# Shield.net
KiCad netlist of a schematic drawn in EAGLE
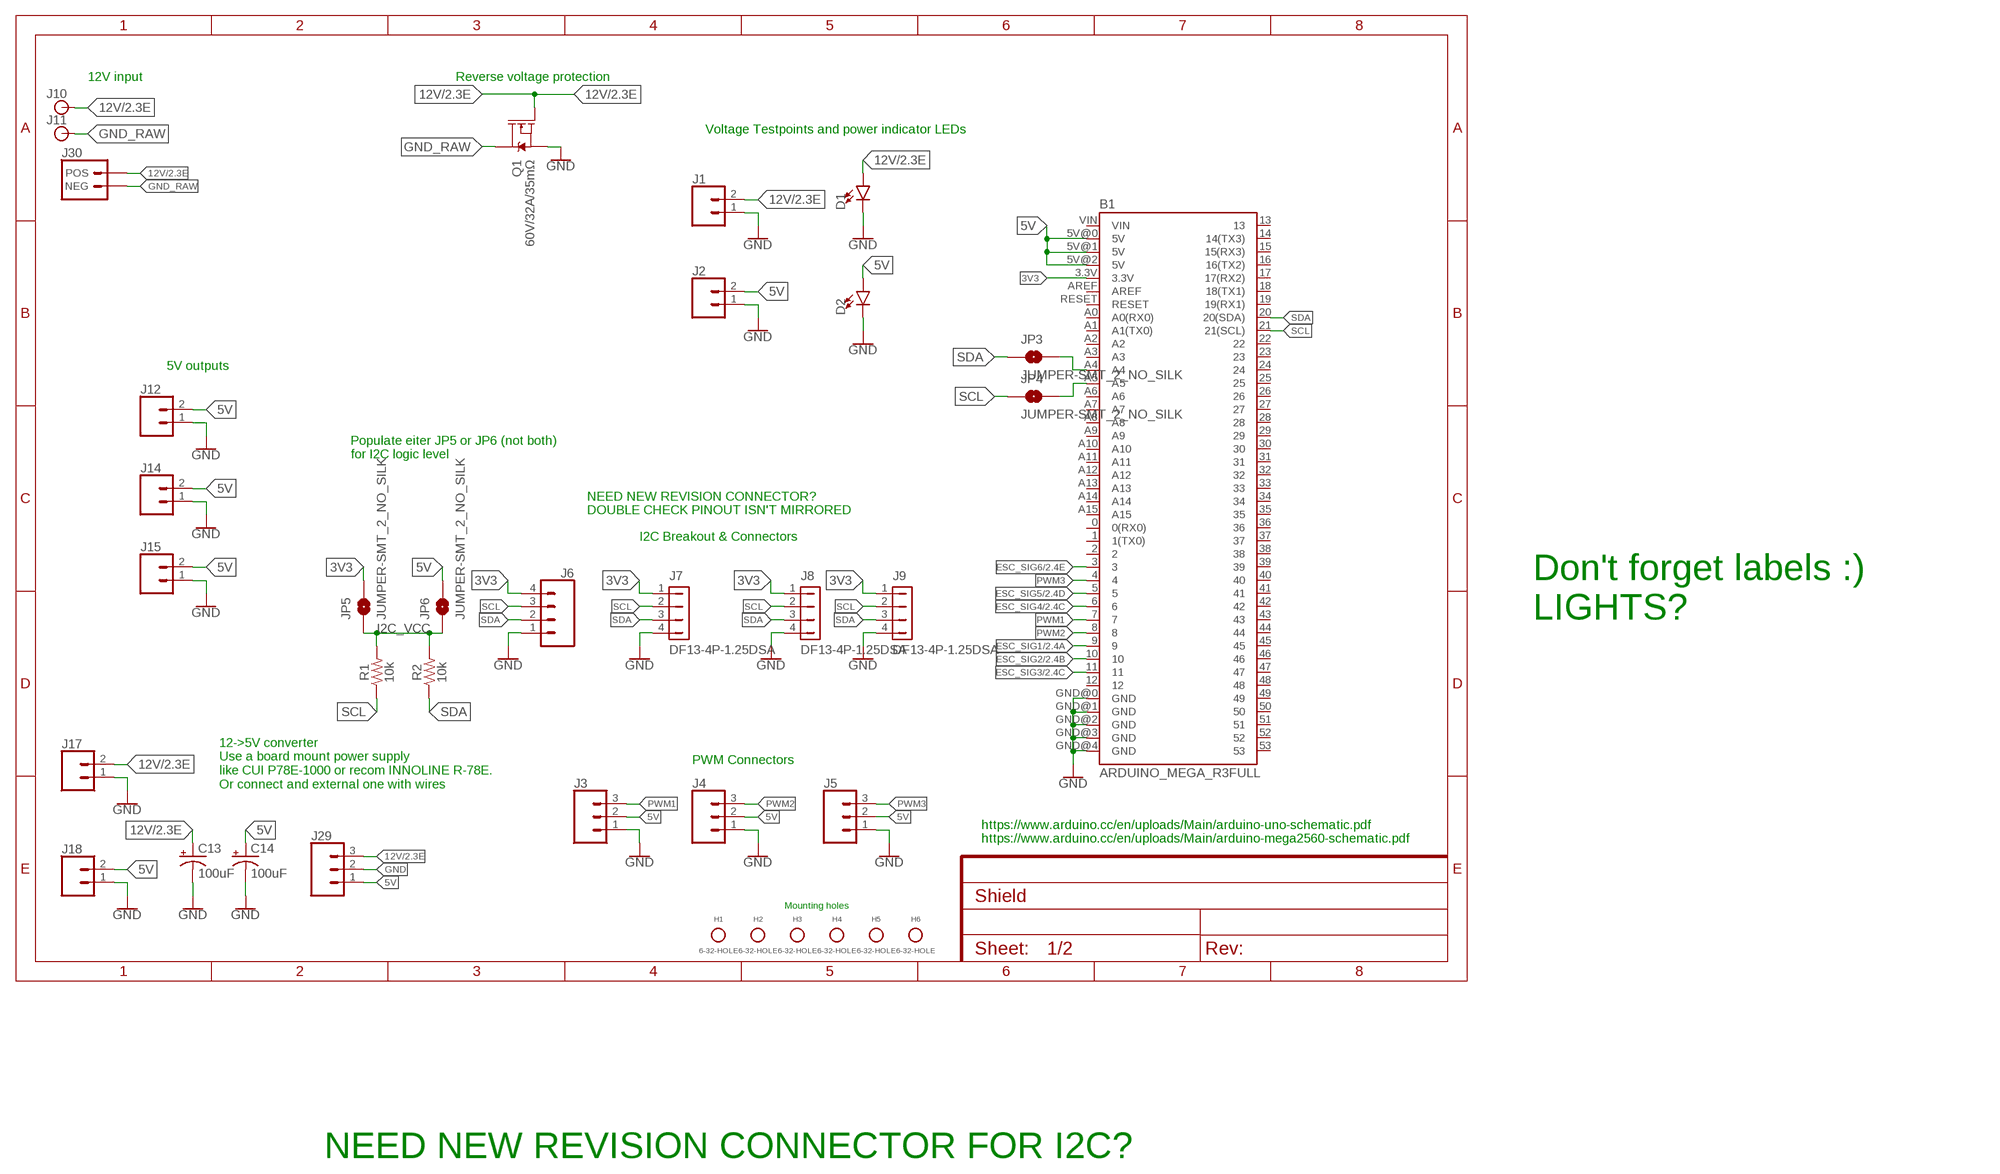
[diagram p0: schematic, sheet 1]
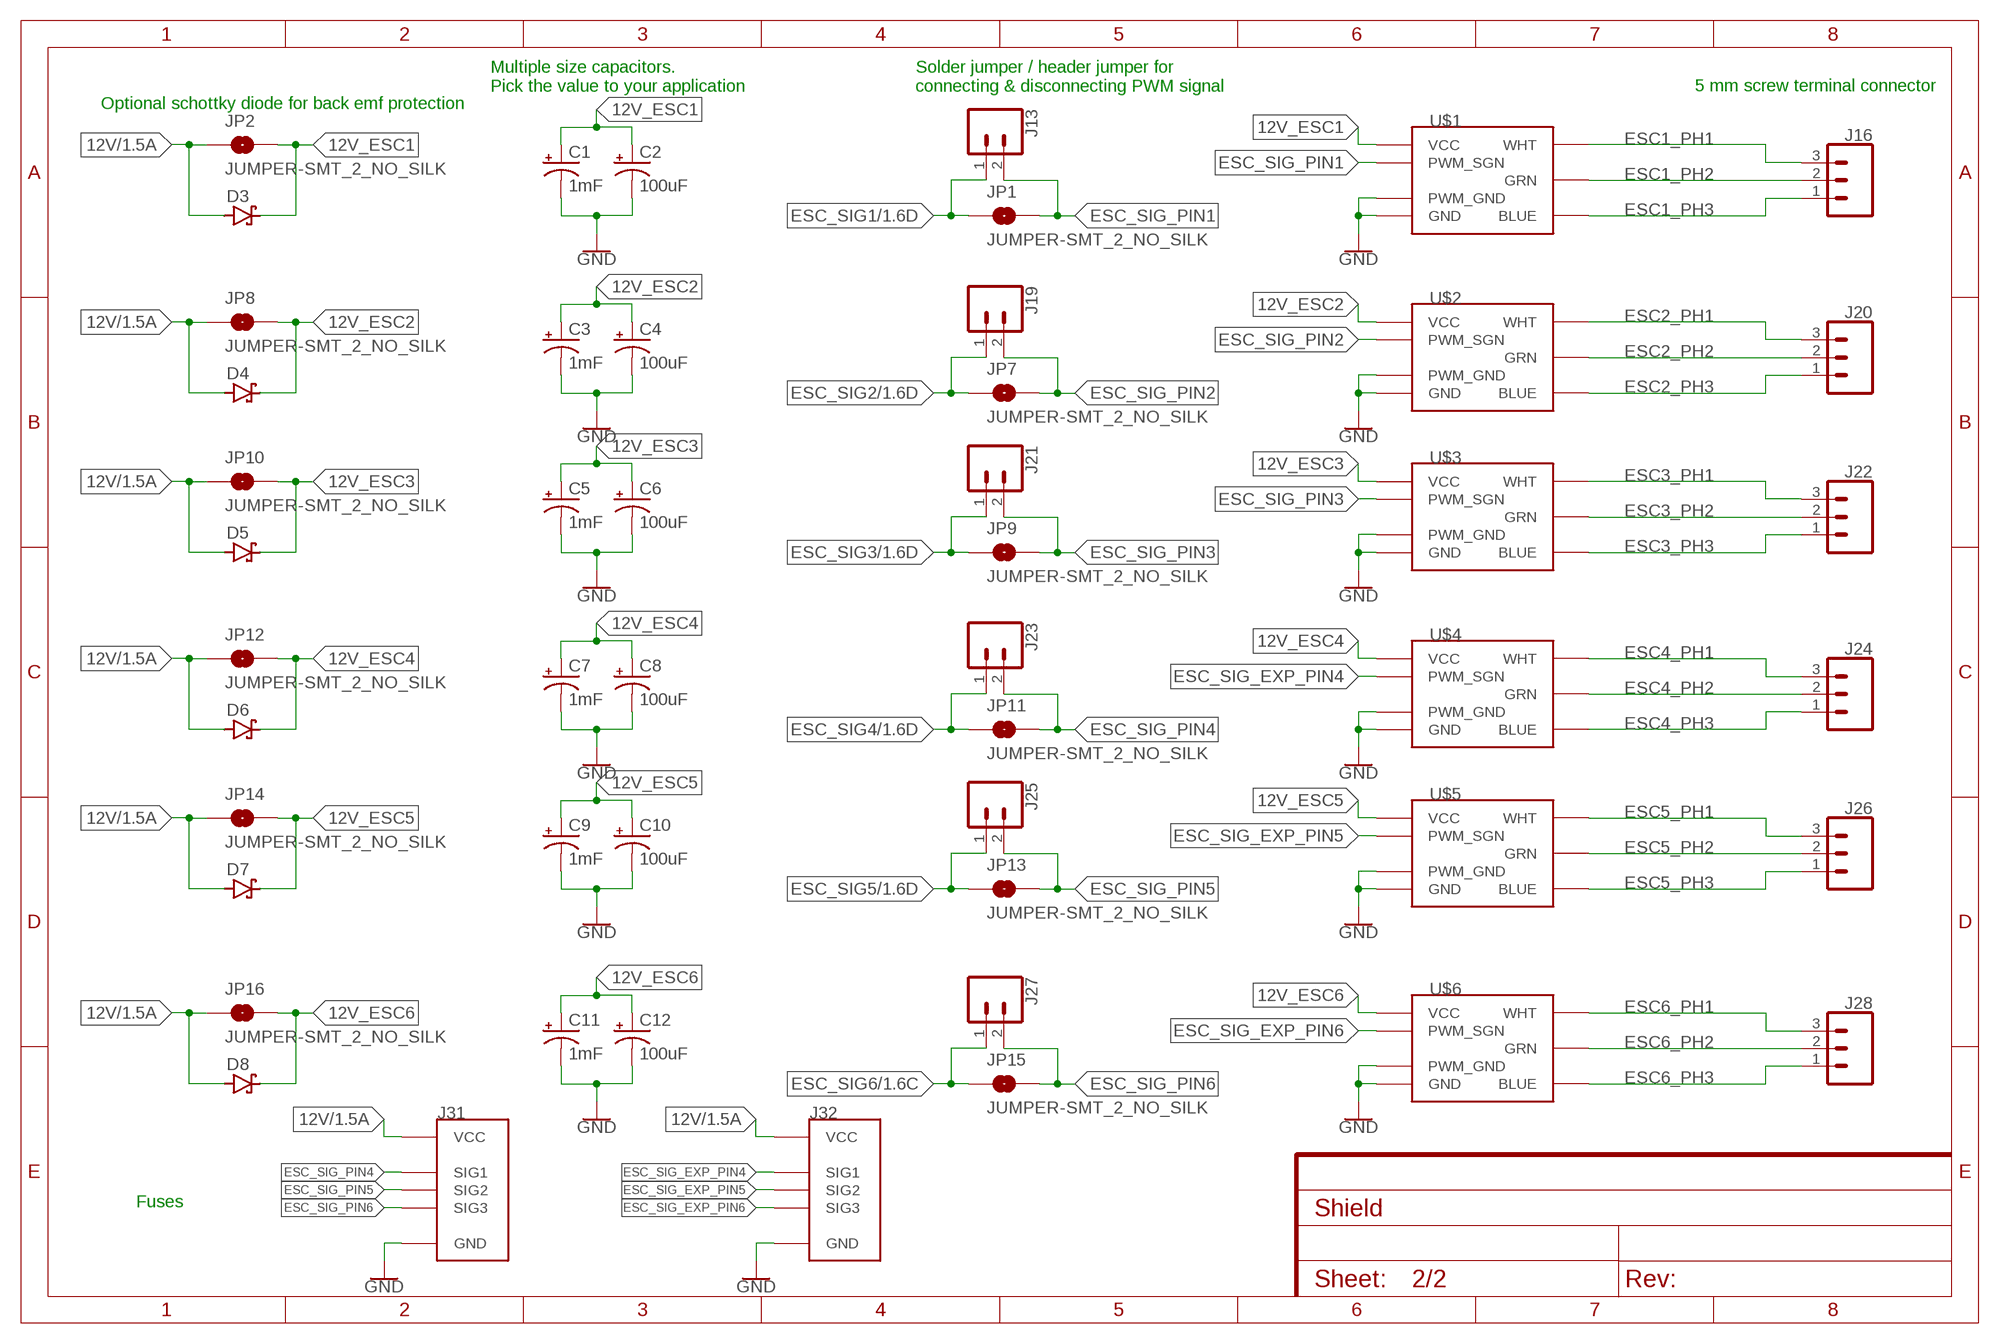
[diagram p1: schematic, sheet 2]

(export (version "E")
  (design (tool "Eeschema 10.0.6"))
  (components
    (comp (ref "B1")
      (value "ARDUINO_MEGA_R3FULL")
      (footprint "eagle-import:ARDUINO_MEGA")
      (libsource (lib "eagle-import") (part "ARDUINO_MEGA_R3FULL"))
    )
    (comp (ref "C13")
      (value "100uF")
      (footprint "eagle-import:CPOL-RADIAL-2.5MM-6.5MM")
      (libsource (lib "eagle-import") (part "100UF-POLAR-RADIAL-2.5MM-25V-20%"))
    )
    (comp (ref "C14")
      (value "100uF")
      (footprint "eagle-import:CPOL-RADIAL-2.5MM-6.5MM")
      (libsource (lib "eagle-import") (part "100UF-POLAR-RADIAL-2.5MM-25V-20%"))
    )
    (comp (ref "D1")
      (value "LED3MM")
      (footprint "eagle-import:LED_3MM")
      (libsource (lib "eagle-import") (part "LED3MM"))
    )
    (comp (ref "D2")
      (value "LED3MM")
      (footprint "eagle-import:LED_3MM")
      (libsource (lib "eagle-import") (part "LED3MM"))
    )
    (comp (ref "H1")
      (value "6-32-HOLE")
      (footprint "eagle-import:6-32-HOLE")
      (libsource (lib "eagle-import") (part "6-32-HOLE"))
    )
    (comp (ref "H2")
      (value "6-32-HOLE")
      (footprint "eagle-import:6-32-HOLE")
      (libsource (lib "eagle-import") (part "6-32-HOLE"))
    )
    (comp (ref "H3")
      (value "6-32-HOLE")
      (footprint "eagle-import:6-32-HOLE")
      (libsource (lib "eagle-import") (part "6-32-HOLE"))
    )
    (comp (ref "H4")
      (value "6-32-HOLE")
      (footprint "eagle-import:6-32-HOLE")
      (libsource (lib "eagle-import") (part "6-32-HOLE"))
    )
    (comp (ref "H5")
      (value "6-32-HOLE")
      (footprint "eagle-import:6-32-HOLE")
      (libsource (lib "eagle-import") (part "6-32-HOLE"))
    )
    (comp (ref "H6")
      (value "6-32-HOLE")
      (footprint "eagle-import:6-32-HOLE")
      (libsource (lib "eagle-import") (part "6-32-HOLE"))
    )
    (comp (ref "J1")
      (value "CONN_02")
      (footprint "eagle-import:1X02")
      (libsource (lib "eagle-import") (part "CONN_02"))
    )
    (comp (ref "J2")
      (value "CONN_02")
      (footprint "eagle-import:1X02")
      (libsource (lib "eagle-import") (part "CONN_02"))
    )
    (comp (ref "J3")
      (value "CONN_03")
      (footprint "eagle-import:1X03")
      (libsource (lib "eagle-import") (part "CONN_03"))
    )
    (comp (ref "J4")
      (value "CONN_03")
      (footprint "eagle-import:1X03")
      (libsource (lib "eagle-import") (part "CONN_03"))
    )
    (comp (ref "J5")
      (value "CONN_03")
      (footprint "eagle-import:1X03")
      (libsource (lib "eagle-import") (part "CONN_03"))
    )
    (comp (ref "J6")
      (value "CONN_04")
      (footprint "eagle-import:1X04")
      (libsource (lib "eagle-import") (part "CONN_04"))
    )
    (comp (ref "J7")
      (value "DF13-4P-1.25DSA")
      (footprint "eagle-import:DF13-4P-1.25DSA")
      (libsource (lib "eagle-import") (part "DF13-4P-1.25DSA"))
    )
    (comp (ref "J8")
      (value "DF13-4P-1.25DSA")
      (footprint "eagle-import:DF13-4P-1.25DSA")
      (libsource (lib "eagle-import") (part "DF13-4P-1.25DSA"))
    )
    (comp (ref "J9")
      (value "DF13-4P-1.25DSA")
      (footprint "eagle-import:DF13-4P-1.25DSA")
      (libsource (lib "eagle-import") (part "DF13-4P-1.25DSA"))
    )
    (comp (ref "J10")
      (value "BANANA_PTH")
      (footprint "eagle-import:BANANA_CONN_NO_THERM")
      (libsource (lib "eagle-import") (part "BANANA_PTH"))
    )
    (comp (ref "J11")
      (value "BANANA_PTH")
      (footprint "eagle-import:BANANA_CONN_NO_THERM")
      (libsource (lib "eagle-import") (part "BANANA_PTH"))
    )
    (comp (ref "J12")
      (value "CONN_02")
      (footprint "eagle-import:1X02")
      (libsource (lib "eagle-import") (part "CONN_02"))
    )
    (comp (ref "J14")
      (value "CONN_02")
      (footprint "eagle-import:1X02")
      (libsource (lib "eagle-import") (part "CONN_02"))
    )
    (comp (ref "J15")
      (value "CONN_02")
      (footprint "eagle-import:1X02")
      (libsource (lib "eagle-import") (part "CONN_02"))
    )
    (comp (ref "J17")
      (value "CONN_02")
      (footprint "eagle-import:1X02")
      (libsource (lib "eagle-import") (part "CONN_02"))
    )
    (comp (ref "J18")
      (value "CONN_02")
      (footprint "eagle-import:1X02")
      (libsource (lib "eagle-import") (part "CONN_02"))
    )
    (comp (ref "J29")
      (value "CONN_03")
      (footprint "eagle-import:1X03")
      (libsource (lib "eagle-import") (part "CONN_03"))
    )
    (comp (ref "J30")
      (value "ANDERON_POWERPOLE_2")
      (footprint "eagle-import:ANDERON_POWERPOLE_2")
      (libsource (lib "eagle-import") (part "ANDERON_POWERPOLE_2"))
    )
    (comp (ref "JP3")
      (value "JUMPER-SMT_2_NO_SILK")
      (footprint "eagle-import:SMT-JUMPER_2_NO_SILK")
      (libsource (lib "eagle-import") (part "JUMPER-SMT_2_NO_SILK"))
    )
    (comp (ref "JP4")
      (value "JUMPER-SMT_2_NO_SILK")
      (footprint "eagle-import:SMT-JUMPER_2_NO_SILK")
      (libsource (lib "eagle-import") (part "JUMPER-SMT_2_NO_SILK"))
    )
    (comp (ref "JP5")
      (value "JUMPER-SMT_2_NO_SILK")
      (footprint "eagle-import:SMT-JUMPER_2_NO_SILK")
      (libsource (lib "eagle-import") (part "JUMPER-SMT_2_NO_SILK"))
    )
    (comp (ref "JP6")
      (value "JUMPER-SMT_2_NO_SILK")
      (footprint "eagle-import:SMT-JUMPER_2_NO_SILK")
      (libsource (lib "eagle-import") (part "JUMPER-SMT_2_NO_SILK"))
    )
    (comp (ref "Q1")
      (value "60V/32A/35mΩ")
      (footprint "eagle-import:TO220V")
      (libsource (lib "eagle-import") (part "MOSFET-NCH-FQP30N06L"))
    )
    (comp (ref "R1")
      (value "10k")
      (footprint "eagle-import:AXIAL-0.3")
      (libsource (lib "eagle-import") (part "10KOHM-HORIZ-1/4W-5%"))
    )
    (comp (ref "R2")
      (value "10k")
      (footprint "eagle-import:AXIAL-0.3")
      (libsource (lib "eagle-import") (part "10KOHM-HORIZ-1/4W-5%"))
    )
    (comp (ref "C1")
      (value "1mF")
      (footprint "eagle-import:CPOL-RADIAL-5MM-10MM")
      (libsource (lib "eagle-import") (part "1000UF-RADIAL-5MM-25V-20%"))
    )
    (comp (ref "C2")
      (value "100uF")
      (footprint "eagle-import:CPOL-RADIAL-2.5MM-6.5MM")
      (libsource (lib "eagle-import") (part "100UF-POLAR-RADIAL-2.5MM-25V-20%"))
    )
    (comp (ref "C3")
      (value "1mF")
      (footprint "eagle-import:CPOL-RADIAL-5MM-10MM")
      (libsource (lib "eagle-import") (part "1000UF-RADIAL-5MM-25V-20%"))
    )
    (comp (ref "C4")
      (value "100uF")
      (footprint "eagle-import:CPOL-RADIAL-2.5MM-6.5MM")
      (libsource (lib "eagle-import") (part "100UF-POLAR-RADIAL-2.5MM-25V-20%"))
    )
    (comp (ref "C5")
      (value "1mF")
      (footprint "eagle-import:CPOL-RADIAL-5MM-10MM")
      (libsource (lib "eagle-import") (part "1000UF-RADIAL-5MM-25V-20%"))
    )
    (comp (ref "C6")
      (value "100uF")
      (footprint "eagle-import:CPOL-RADIAL-2.5MM-6.5MM")
      (libsource (lib "eagle-import") (part "100UF-POLAR-RADIAL-2.5MM-25V-20%"))
    )
    (comp (ref "C7")
      (value "1mF")
      (footprint "eagle-import:CPOL-RADIAL-5MM-10MM")
      (libsource (lib "eagle-import") (part "1000UF-RADIAL-5MM-25V-20%"))
    )
    (comp (ref "C8")
      (value "100uF")
      (footprint "eagle-import:CPOL-RADIAL-2.5MM-6.5MM")
      (libsource (lib "eagle-import") (part "100UF-POLAR-RADIAL-2.5MM-25V-20%"))
    )
    (comp (ref "C9")
      (value "1mF")
      (footprint "eagle-import:CPOL-RADIAL-5MM-10MM")
      (libsource (lib "eagle-import") (part "1000UF-RADIAL-5MM-25V-20%"))
    )
    (comp (ref "C10")
      (value "100uF")
      (footprint "eagle-import:CPOL-RADIAL-2.5MM-6.5MM")
      (libsource (lib "eagle-import") (part "100UF-POLAR-RADIAL-2.5MM-25V-20%"))
    )
    (comp (ref "C11")
      (value "1mF")
      (footprint "eagle-import:CPOL-RADIAL-5MM-10MM")
      (libsource (lib "eagle-import") (part "1000UF-RADIAL-5MM-25V-20%"))
    )
    (comp (ref "C12")
      (value "100uF")
      (footprint "eagle-import:CPOL-RADIAL-2.5MM-6.5MM")
      (libsource (lib "eagle-import") (part "100UF-POLAR-RADIAL-2.5MM-25V-20%"))
    )
    (comp (ref "D3")
      (value "SCHOTTKY-DIODECB429-15")
      (footprint "eagle-import:CB429-15")
      (libsource (lib "eagle-import") (part "SCHOTTKY-DIODECB429-15"))
    )
    (comp (ref "D4")
      (value "SCHOTTKY-DIODECB429-15")
      (footprint "eagle-import:CB429-15")
      (libsource (lib "eagle-import") (part "SCHOTTKY-DIODECB429-15"))
    )
    (comp (ref "D5")
      (value "SCHOTTKY-DIODECB429-15")
      (footprint "eagle-import:CB429-15")
      (libsource (lib "eagle-import") (part "SCHOTTKY-DIODECB429-15"))
    )
    (comp (ref "D6")
      (value "SCHOTTKY-DIODECB429-15")
      (footprint "eagle-import:CB429-15")
      (libsource (lib "eagle-import") (part "SCHOTTKY-DIODECB429-15"))
    )
    (comp (ref "D7")
      (value "SCHOTTKY-DIODECB429-15")
      (footprint "eagle-import:CB429-15")
      (libsource (lib "eagle-import") (part "SCHOTTKY-DIODECB429-15"))
    )
    (comp (ref "D8")
      (value "SCHOTTKY-DIODECB429-15")
      (footprint "eagle-import:CB429-15")
      (libsource (lib "eagle-import") (part "SCHOTTKY-DIODECB429-15"))
    )
    (comp (ref "J13")
      (value "CONN_02")
      (footprint "eagle-import:1X02")
      (libsource (lib "eagle-import") (part "CONN_02"))
    )
    (comp (ref "J16")
      (value "CONN_03-SCREW-5MM")
      (footprint "eagle-import:SCREWTERMINAL-5MM-3")
      (libsource (lib "eagle-import") (part "CONN_03-SCREW-5MM"))
    )
    (comp (ref "J19")
      (value "CONN_02")
      (footprint "eagle-import:1X02")
      (libsource (lib "eagle-import") (part "CONN_02"))
    )
    (comp (ref "J20")
      (value "CONN_03-SCREW-5MM")
      (footprint "eagle-import:SCREWTERMINAL-5MM-3")
      (libsource (lib "eagle-import") (part "CONN_03-SCREW-5MM"))
    )
    (comp (ref "J21")
      (value "CONN_02")
      (footprint "eagle-import:1X02")
      (libsource (lib "eagle-import") (part "CONN_02"))
    )
    (comp (ref "J22")
      (value "CONN_03-SCREW-5MM")
      (footprint "eagle-import:SCREWTERMINAL-5MM-3")
      (libsource (lib "eagle-import") (part "CONN_03-SCREW-5MM"))
    )
    (comp (ref "J23")
      (value "CONN_02")
      (footprint "eagle-import:1X02")
      (libsource (lib "eagle-import") (part "CONN_02"))
    )
    (comp (ref "J24")
      (value "CONN_03-SCREW-5MM")
      (footprint "eagle-import:SCREWTERMINAL-5MM-3")
      (libsource (lib "eagle-import") (part "CONN_03-SCREW-5MM"))
    )
    (comp (ref "J25")
      (value "CONN_02")
      (footprint "eagle-import:1X02")
      (libsource (lib "eagle-import") (part "CONN_02"))
    )
    (comp (ref "J26")
      (value "CONN_03-SCREW-5MM")
      (footprint "eagle-import:SCREWTERMINAL-5MM-3")
      (libsource (lib "eagle-import") (part "CONN_03-SCREW-5MM"))
    )
    (comp (ref "J27")
      (value "CONN_02")
      (footprint "eagle-import:1X02")
      (libsource (lib "eagle-import") (part "CONN_02"))
    )
    (comp (ref "J28")
      (value "CONN_03-SCREW-5MM")
      (footprint "eagle-import:SCREWTERMINAL-5MM-3")
      (libsource (lib "eagle-import") (part "CONN_03-SCREW-5MM"))
    )
    (comp (ref "J31")
      (value "ESC_EXPANSION_CONNECTOR")
      (footprint "eagle-import:EXPANSION")
      (libsource (lib "eagle-import") (part "ESC_EXPANSION_CONNECTOR"))
    )
    (comp (ref "J32")
      (value "ESC_EXPANSION_CONNECTOR")
      (footprint "eagle-import:EXPANSION")
      (libsource (lib "eagle-import") (part "ESC_EXPANSION_CONNECTOR"))
    )
    (comp (ref "JP1")
      (value "JUMPER-SMT_2_NO_SILK")
      (footprint "eagle-import:SMT-JUMPER_2_NO_SILK")
      (libsource (lib "eagle-import") (part "JUMPER-SMT_2_NO_SILK"))
    )
    (comp (ref "JP2")
      (value "JUMPER-SMT_2_NO_SILK")
      (footprint "eagle-import:SMT-JUMPER_2_NO_SILK")
      (libsource (lib "eagle-import") (part "JUMPER-SMT_2_NO_SILK"))
    )
    (comp (ref "JP7")
      (value "JUMPER-SMT_2_NO_SILK")
      (footprint "eagle-import:SMT-JUMPER_2_NO_SILK")
      (libsource (lib "eagle-import") (part "JUMPER-SMT_2_NO_SILK"))
    )
    (comp (ref "JP8")
      (value "JUMPER-SMT_2_NO_SILK")
      (footprint "eagle-import:SMT-JUMPER_2_NO_SILK")
      (libsource (lib "eagle-import") (part "JUMPER-SMT_2_NO_SILK"))
    )
    (comp (ref "JP9")
      (value "JUMPER-SMT_2_NO_SILK")
      (footprint "eagle-import:SMT-JUMPER_2_NO_SILK")
      (libsource (lib "eagle-import") (part "JUMPER-SMT_2_NO_SILK"))
    )
    (comp (ref "JP10")
      (value "JUMPER-SMT_2_NO_SILK")
      (footprint "eagle-import:SMT-JUMPER_2_NO_SILK")
      (libsource (lib "eagle-import") (part "JUMPER-SMT_2_NO_SILK"))
    )
    (comp (ref "JP11")
      (value "JUMPER-SMT_2_NO_SILK")
      (footprint "eagle-import:SMT-JUMPER_2_NO_SILK")
      (libsource (lib "eagle-import") (part "JUMPER-SMT_2_NO_SILK"))
    )
    (comp (ref "JP12")
      (value "JUMPER-SMT_2_NO_SILK")
      (footprint "eagle-import:SMT-JUMPER_2_NO_SILK")
      (libsource (lib "eagle-import") (part "JUMPER-SMT_2_NO_SILK"))
    )
    (comp (ref "JP13")
      (value "JUMPER-SMT_2_NO_SILK")
      (footprint "eagle-import:SMT-JUMPER_2_NO_SILK")
      (libsource (lib "eagle-import") (part "JUMPER-SMT_2_NO_SILK"))
    )
    (comp (ref "JP14")
      (value "JUMPER-SMT_2_NO_SILK")
      (footprint "eagle-import:SMT-JUMPER_2_NO_SILK")
      (libsource (lib "eagle-import") (part "JUMPER-SMT_2_NO_SILK"))
    )
    (comp (ref "JP15")
      (value "JUMPER-SMT_2_NO_SILK")
      (footprint "eagle-import:SMT-JUMPER_2_NO_SILK")
      (libsource (lib "eagle-import") (part "JUMPER-SMT_2_NO_SILK"))
    )
    (comp (ref "JP16")
      (value "JUMPER-SMT_2_NO_SILK")
      (footprint "eagle-import:SMT-JUMPER_2_NO_SILK")
      (libsource (lib "eagle-import") (part "JUMPER-SMT_2_NO_SILK"))
    )
    (comp (ref "U$1")
      (value "ESC")
      (footprint "eagle-import:ESC")
      (libsource (lib "eagle-import") (part "ESC"))
    )
    (comp (ref "U$2")
      (value "ESC")
      (footprint "eagle-import:ESC")
      (libsource (lib "eagle-import") (part "ESC"))
    )
    (comp (ref "U$3")
      (value "ESC")
      (footprint "eagle-import:ESC")
      (libsource (lib "eagle-import") (part "ESC"))
    )
    (comp (ref "U$4")
      (value "ESC")
      (footprint "eagle-import:ESC")
      (libsource (lib "eagle-import") (part "ESC"))
    )
    (comp (ref "U$5")
      (value "ESC")
      (footprint "eagle-import:ESC")
      (libsource (lib "eagle-import") (part "ESC"))
    )
    (comp (ref "U$6")
      (value "ESC")
      (footprint "eagle-import:ESC")
      (libsource (lib "eagle-import") (part "ESC"))
    )
  )
  (nets
    (net (code "1") (name "3V3") (class "Default")
      (node (ref "B1") (pin "3.3V") (pinfunction "3.3V_3.3V") (pintype "bidirectional"))
      (node (ref "J6") (pin "4") (pinfunction "4_4") (pintype "passive"))
      (node (ref "J7") (pin "1") (pinfunction "1_1") (pintype "passive"))
      (node (ref "J8") (pin "1") (pinfunction "1_1") (pintype "passive"))
      (node (ref "J9") (pin "1") (pinfunction "1_1") (pintype "passive"))
      (node (ref "JP5") (pin "2") (pinfunction "2_2") (pintype "passive"))
    )
    (net (code "2") (name "5V") (class "Default")
      (node (ref "B1") (pin "5V@0") (pinfunction "5V_5V@0") (pintype "bidirectional"))
      (node (ref "B1") (pin "5V@1") (pinfunction "5V_5V@1") (pintype "bidirectional"))
      (node (ref "B1") (pin "5V@2") (pinfunction "5V_5V@2") (pintype "bidirectional"))
      (node (ref "C14") (pin "1") (pinfunction "+_1") (pintype "passive"))
      (node (ref "D2") (pin "A") (pinfunction "A_A") (pintype "passive"))
      (node (ref "J12") (pin "2") (pinfunction "2_2") (pintype "passive"))
      (node (ref "J14") (pin "2") (pinfunction "2_2") (pintype "passive"))
      (node (ref "J15") (pin "2") (pinfunction "2_2") (pintype "passive"))
      (node (ref "J18") (pin "2") (pinfunction "2_2") (pintype "passive"))
      (node (ref "J2") (pin "2") (pinfunction "2_2") (pintype "passive"))
      (node (ref "J29") (pin "1") (pinfunction "1_1") (pintype "passive"))
      (node (ref "J3") (pin "2") (pinfunction "2_2") (pintype "passive"))
      (node (ref "J4") (pin "2") (pinfunction "2_2") (pintype "passive"))
      (node (ref "J5") (pin "2") (pinfunction "2_2") (pintype "passive"))
      (node (ref "JP6") (pin "2") (pinfunction "2_2") (pintype "passive"))
    )
    (net (code "3") (name "12V") (class "Default")
      (node (ref "C13") (pin "1") (pinfunction "+_1") (pintype "passive"))
      (node (ref "D1") (pin "A") (pinfunction "A_A") (pintype "passive"))
      (node (ref "D3") (pin "A") (pinfunction "A_A") (pintype "passive"))
      (node (ref "D4") (pin "A") (pinfunction "A_A") (pintype "passive"))
      (node (ref "D5") (pin "A") (pinfunction "A_A") (pintype "passive"))
      (node (ref "D6") (pin "A") (pinfunction "A_A") (pintype "passive"))
      (node (ref "D7") (pin "A") (pinfunction "A_A") (pintype "passive"))
      (node (ref "D8") (pin "A") (pinfunction "A_A") (pintype "passive"))
      (node (ref "J1") (pin "2") (pinfunction "2_2") (pintype "passive"))
      (node (ref "J10") (pin "1") (pinfunction "1_1") (pintype "passive"))
      (node (ref "J17") (pin "2") (pinfunction "2_2") (pintype "passive"))
      (node (ref "J29") (pin "3") (pinfunction "3_3") (pintype "passive"))
      (node (ref "J30") (pin "POS") (pinfunction "POS_POS") (pintype "power_in"))
      (node (ref "J31") (pin "15") (pinfunction "VCC_15") (pintype "power_in"))
      (node (ref "J31") (pin "16") (pinfunction "VCC_16") (pintype "power_in"))
      (node (ref "J31") (pin "17") (pinfunction "VCC_17") (pintype "power_in"))
      (node (ref "J31") (pin "18") (pinfunction "VCC_18") (pintype "power_in"))
      (node (ref "J31") (pin "19") (pinfunction "VCC_19") (pintype "power_in"))
      (node (ref "J31") (pin "20") (pinfunction "VCC_20") (pintype "power_in"))
      (node (ref "J31") (pin "21") (pinfunction "VCC_21") (pintype "power_in"))
      (node (ref "J31") (pin "22") (pinfunction "VCC_22") (pintype "power_in"))
      (node (ref "J31") (pin "23") (pinfunction "VCC_23") (pintype "power_in"))
      (node (ref "J31") (pin "24") (pinfunction "VCC_24") (pintype "power_in"))
      (node (ref "J32") (pin "15") (pinfunction "VCC_15") (pintype "power_in"))
      (node (ref "J32") (pin "16") (pinfunction "VCC_16") (pintype "power_in"))
      (node (ref "J32") (pin "17") (pinfunction "VCC_17") (pintype "power_in"))
      (node (ref "J32") (pin "18") (pinfunction "VCC_18") (pintype "power_in"))
      (node (ref "J32") (pin "19") (pinfunction "VCC_19") (pintype "power_in"))
      (node (ref "J32") (pin "20") (pinfunction "VCC_20") (pintype "power_in"))
      (node (ref "J32") (pin "21") (pinfunction "VCC_21") (pintype "power_in"))
      (node (ref "J32") (pin "22") (pinfunction "VCC_22") (pintype "power_in"))
      (node (ref "J32") (pin "23") (pinfunction "VCC_23") (pintype "power_in"))
      (node (ref "J32") (pin "24") (pinfunction "VCC_24") (pintype "power_in"))
      (node (ref "JP10") (pin "1") (pinfunction "1_1") (pintype "passive"))
      (node (ref "JP12") (pin "1") (pinfunction "1_1") (pintype "passive"))
      (node (ref "JP14") (pin "1") (pinfunction "1_1") (pintype "passive"))
      (node (ref "JP16") (pin "1") (pinfunction "1_1") (pintype "passive"))
      (node (ref "JP2") (pin "1") (pinfunction "1_1") (pintype "passive"))
      (node (ref "JP8") (pin "1") (pinfunction "1_1") (pintype "passive"))
      (node (ref "Q1") (pin "1") (pinfunction "G_1") (pintype "bidirectional"))
    )
    (net (code "4") (name "12V_ESC1") (class "Default")
      (node (ref "C1") (pin "+") (pinfunction "+_+") (pintype "passive"))
      (node (ref "C2") (pin "1") (pinfunction "+_1") (pintype "passive"))
      (node (ref "D3") (pin "C") (pinfunction "C_C") (pintype "passive"))
      (node (ref "JP2") (pin "2") (pinfunction "2_2") (pintype "passive"))
      (node (ref "U$1") (pin "VCC") (pinfunction "VCC_VCC") (pintype "power_in"))
    )
    (net (code "5") (name "12V_ESC2") (class "Default")
      (node (ref "C3") (pin "+") (pinfunction "+_+") (pintype "passive"))
      (node (ref "C4") (pin "1") (pinfunction "+_1") (pintype "passive"))
      (node (ref "D4") (pin "C") (pinfunction "C_C") (pintype "passive"))
      (node (ref "JP8") (pin "2") (pinfunction "2_2") (pintype "passive"))
      (node (ref "U$2") (pin "VCC") (pinfunction "VCC_VCC") (pintype "power_in"))
    )
    (net (code "6") (name "12V_ESC3") (class "Default")
      (node (ref "C5") (pin "+") (pinfunction "+_+") (pintype "passive"))
      (node (ref "C6") (pin "1") (pinfunction "+_1") (pintype "passive"))
      (node (ref "D5") (pin "C") (pinfunction "C_C") (pintype "passive"))
      (node (ref "JP10") (pin "2") (pinfunction "2_2") (pintype "passive"))
      (node (ref "U$3") (pin "VCC") (pinfunction "VCC_VCC") (pintype "power_in"))
    )
    (net (code "7") (name "12V_ESC4") (class "Default")
      (node (ref "C7") (pin "+") (pinfunction "+_+") (pintype "passive"))
      (node (ref "C8") (pin "1") (pinfunction "+_1") (pintype "passive"))
      (node (ref "D6") (pin "C") (pinfunction "C_C") (pintype "passive"))
      (node (ref "JP12") (pin "2") (pinfunction "2_2") (pintype "passive"))
      (node (ref "U$4") (pin "VCC") (pinfunction "VCC_VCC") (pintype "power_in"))
    )
    (net (code "8") (name "12V_ESC5") (class "Default")
      (node (ref "C10") (pin "1") (pinfunction "+_1") (pintype "passive"))
      (node (ref "C9") (pin "+") (pinfunction "+_+") (pintype "passive"))
      (node (ref "D7") (pin "C") (pinfunction "C_C") (pintype "passive"))
      (node (ref "JP14") (pin "2") (pinfunction "2_2") (pintype "passive"))
      (node (ref "U$5") (pin "VCC") (pinfunction "VCC_VCC") (pintype "power_in"))
    )
    (net (code "9") (name "12V_ESC6") (class "Default")
      (node (ref "C11") (pin "+") (pinfunction "+_+") (pintype "passive"))
      (node (ref "C12") (pin "1") (pinfunction "+_1") (pintype "passive"))
      (node (ref "D8") (pin "C") (pinfunction "C_C") (pintype "passive"))
      (node (ref "JP16") (pin "2") (pinfunction "2_2") (pintype "passive"))
      (node (ref "U$6") (pin "VCC") (pinfunction "VCC_VCC") (pintype "power_in"))
    )
    (net (code "10") (name "ESC1_PH1") (class "Default")
      (node (ref "J16") (pin "3") (pinfunction "3_3") (pintype "passive"))
      (node (ref "U$1") (pin "BLUE") (pinfunction "WHT_BLUE") (pintype "output"))
    )
    (net (code "11") (name "ESC1_PH2") (class "Default")
      (node (ref "J16") (pin "2") (pinfunction "2_2") (pintype "passive"))
      (node (ref "U$1") (pin "GRN") (pinfunction "GRN_GRN") (pintype "output"))
    )
    (net (code "12") (name "ESC1_PH3") (class "Default")
      (node (ref "J16") (pin "1") (pinfunction "1_1") (pintype "passive"))
      (node (ref "U$1") (pin "WHT") (pinfunction "BLUE_WHT") (pintype "output"))
    )
    (net (code "13") (name "ESC2_PH1") (class "Default")
      (node (ref "J20") (pin "3") (pinfunction "3_3") (pintype "passive"))
      (node (ref "U$2") (pin "BLUE") (pinfunction "WHT_BLUE") (pintype "output"))
    )
    (net (code "14") (name "ESC2_PH2") (class "Default")
      (node (ref "J20") (pin "2") (pinfunction "2_2") (pintype "passive"))
      (node (ref "U$2") (pin "GRN") (pinfunction "GRN_GRN") (pintype "output"))
    )
    (net (code "15") (name "ESC2_PH3") (class "Default")
      (node (ref "J20") (pin "1") (pinfunction "1_1") (pintype "passive"))
      (node (ref "U$2") (pin "WHT") (pinfunction "BLUE_WHT") (pintype "output"))
    )
    (net (code "16") (name "ESC3_PH1") (class "Default")
      (node (ref "J22") (pin "3") (pinfunction "3_3") (pintype "passive"))
      (node (ref "U$3") (pin "BLUE") (pinfunction "WHT_BLUE") (pintype "output"))
    )
    (net (code "17") (name "ESC3_PH2") (class "Default")
      (node (ref "J22") (pin "2") (pinfunction "2_2") (pintype "passive"))
      (node (ref "U$3") (pin "GRN") (pinfunction "GRN_GRN") (pintype "output"))
    )
    (net (code "18") (name "ESC3_PH3") (class "Default")
      (node (ref "J22") (pin "1") (pinfunction "1_1") (pintype "passive"))
      (node (ref "U$3") (pin "WHT") (pinfunction "BLUE_WHT") (pintype "output"))
    )
    (net (code "19") (name "ESC4_PH1") (class "Default")
      (node (ref "J24") (pin "3") (pinfunction "3_3") (pintype "passive"))
      (node (ref "U$4") (pin "BLUE") (pinfunction "WHT_BLUE") (pintype "output"))
    )
    (net (code "20") (name "ESC4_PH2") (class "Default")
      (node (ref "J24") (pin "2") (pinfunction "2_2") (pintype "passive"))
      (node (ref "U$4") (pin "GRN") (pinfunction "GRN_GRN") (pintype "output"))
    )
    (net (code "21") (name "ESC4_PH3") (class "Default")
      (node (ref "J24") (pin "1") (pinfunction "1_1") (pintype "passive"))
      (node (ref "U$4") (pin "WHT") (pinfunction "BLUE_WHT") (pintype "output"))
    )
    (net (code "22") (name "ESC5_PH1") (class "Default")
      (node (ref "J26") (pin "3") (pinfunction "3_3") (pintype "passive"))
      (node (ref "U$5") (pin "BLUE") (pinfunction "WHT_BLUE") (pintype "output"))
    )
    (net (code "23") (name "ESC5_PH2") (class "Default")
      (node (ref "J26") (pin "2") (pinfunction "2_2") (pintype "passive"))
      (node (ref "U$5") (pin "GRN") (pinfunction "GRN_GRN") (pintype "output"))
    )
    (net (code "24") (name "ESC5_PH3") (class "Default")
      (node (ref "J26") (pin "1") (pinfunction "1_1") (pintype "passive"))
      (node (ref "U$5") (pin "WHT") (pinfunction "BLUE_WHT") (pintype "output"))
    )
    (net (code "25") (name "ESC6_PH1") (class "Default")
      (node (ref "J28") (pin "3") (pinfunction "3_3") (pintype "passive"))
      (node (ref "U$6") (pin "BLUE") (pinfunction "WHT_BLUE") (pintype "output"))
    )
    (net (code "26") (name "ESC6_PH2") (class "Default")
      (node (ref "J28") (pin "2") (pinfunction "2_2") (pintype "passive"))
      (node (ref "U$6") (pin "GRN") (pinfunction "GRN_GRN") (pintype "output"))
    )
    (net (code "27") (name "ESC6_PH3") (class "Default")
      (node (ref "J28") (pin "1") (pinfunction "1_1") (pintype "passive"))
      (node (ref "U$6") (pin "WHT") (pinfunction "BLUE_WHT") (pintype "output"))
    )
    (net (code "28") (name "ESC_SIG1") (class "Default")
      (node (ref "B1") (pin "9") (pinfunction "9_9") (pintype "bidirectional"))
      (node (ref "J13") (pin "1") (pinfunction "1_1") (pintype "passive"))
      (node (ref "JP1") (pin "1") (pinfunction "1_1") (pintype "passive"))
    )
    (net (code "29") (name "ESC_SIG2") (class "Default")
      (node (ref "B1") (pin "10") (pinfunction "10_10") (pintype "bidirectional"))
      (node (ref "J19") (pin "1") (pinfunction "1_1") (pintype "passive"))
      (node (ref "JP7") (pin "1") (pinfunction "1_1") (pintype "passive"))
    )
    (net (code "30") (name "ESC_SIG3") (class "Default")
      (node (ref "B1") (pin "11") (pinfunction "11_11") (pintype "bidirectional"))
      (node (ref "J21") (pin "1") (pinfunction "1_1") (pintype "passive"))
      (node (ref "JP9") (pin "1") (pinfunction "1_1") (pintype "passive"))
    )
    (net (code "31") (name "ESC_SIG4") (class "Default")
      (node (ref "B1") (pin "6") (pinfunction "6_6") (pintype "bidirectional"))
      (node (ref "J23") (pin "1") (pinfunction "1_1") (pintype "passive"))
      (node (ref "JP11") (pin "1") (pinfunction "1_1") (pintype "passive"))
    )
    (net (code "32") (name "ESC_SIG5") (class "Default")
      (node (ref "B1") (pin "5") (pinfunction "5_5") (pintype "bidirectional"))
      (node (ref "J25") (pin "1") (pinfunction "1_1") (pintype "passive"))
      (node (ref "JP13") (pin "1") (pinfunction "1_1") (pintype "passive"))
    )
    (net (code "33") (name "ESC_SIG6") (class "Default")
      (node (ref "B1") (pin "3") (pinfunction "3_3") (pintype "bidirectional"))
      (node (ref "J27") (pin "1") (pinfunction "1_1") (pintype "passive"))
      (node (ref "JP15") (pin "1") (pinfunction "1_1") (pintype "passive"))
    )
    (net (code "34") (name "ESC_SIG_EXP_PIN4") (class "Default")
      (node (ref "J32") (pin "11") (pinfunction "SIG1_11") (pintype "bidirectional"))
      (node (ref "U$4") (pin "PWM_SGN") (pinfunction "PWM_SGN_PWM_SGN") (pintype "input"))
    )
    (net (code "35") (name "ESC_SIG_EXP_PIN5") (class "Default")
      (node (ref "J32") (pin "12") (pinfunction "SIG2_12") (pintype "bidirectional"))
      (node (ref "U$5") (pin "PWM_SGN") (pinfunction "PWM_SGN_PWM_SGN") (pintype "input"))
    )
    (net (code "36") (name "ESC_SIG_EXP_PIN6") (class "Default")
      (node (ref "J32") (pin "13") (pinfunction "SIG3_13") (pintype "bidirectional"))
      (node (ref "U$6") (pin "PWM_SGN") (pinfunction "PWM_SGN_PWM_SGN") (pintype "input"))
    )
    (net (code "37") (name "ESC_SIG_PIN1") (class "Default")
      (node (ref "J13") (pin "2") (pinfunction "2_2") (pintype "passive"))
      (node (ref "JP1") (pin "2") (pinfunction "2_2") (pintype "passive"))
      (node (ref "U$1") (pin "PWM_SGN") (pinfunction "PWM_SGN_PWM_SGN") (pintype "input"))
    )
    (net (code "38") (name "ESC_SIG_PIN2") (class "Default")
      (node (ref "J19") (pin "2") (pinfunction "2_2") (pintype "passive"))
      (node (ref "JP7") (pin "2") (pinfunction "2_2") (pintype "passive"))
      (node (ref "U$2") (pin "PWM_SGN") (pinfunction "PWM_SGN_PWM_SGN") (pintype "input"))
    )
    (net (code "39") (name "ESC_SIG_PIN3") (class "Default")
      (node (ref "J21") (pin "2") (pinfunction "2_2") (pintype "passive"))
      (node (ref "JP9") (pin "2") (pinfunction "2_2") (pintype "passive"))
      (node (ref "U$3") (pin "PWM_SGN") (pinfunction "PWM_SGN_PWM_SGN") (pintype "input"))
    )
    (net (code "40") (name "ESC_SIG_PIN4") (class "Default")
      (node (ref "J23") (pin "2") (pinfunction "2_2") (pintype "passive"))
      (node (ref "J31") (pin "11") (pinfunction "SIG1_11") (pintype "bidirectional"))
      (node (ref "JP11") (pin "2") (pinfunction "2_2") (pintype "passive"))
    )
    (net (code "41") (name "ESC_SIG_PIN5") (class "Default")
      (node (ref "J25") (pin "2") (pinfunction "2_2") (pintype "passive"))
      (node (ref "J31") (pin "12") (pinfunction "SIG2_12") (pintype "bidirectional"))
      (node (ref "JP13") (pin "2") (pinfunction "2_2") (pintype "passive"))
    )
    (net (code "42") (name "ESC_SIG_PIN6") (class "Default")
      (node (ref "J27") (pin "2") (pinfunction "2_2") (pintype "passive"))
      (node (ref "J31") (pin "13") (pinfunction "SIG3_13") (pintype "bidirectional"))
      (node (ref "JP15") (pin "2") (pinfunction "2_2") (pintype "passive"))
    )
    (net (code "43") (name "GND") (class "Default")
      (node (ref "B1") (pin "GND@0") (pinfunction "GND_GND@0") (pintype "bidirectional"))
      (node (ref "B1") (pin "GND@1") (pinfunction "GND_GND@1") (pintype "bidirectional"))
      (node (ref "B1") (pin "GND@2") (pinfunction "GND_GND@2") (pintype "bidirectional"))
      (node (ref "B1") (pin "GND@3") (pinfunction "GND_GND@3") (pintype "bidirectional"))
      (node (ref "B1") (pin "GND@4") (pinfunction "GND_GND@4") (pintype "bidirectional"))
      (node (ref "C1") (pin "-") (pinfunction "-_-") (pintype "passive"))
      (node (ref "C10") (pin "2") (pinfunction "-_2") (pintype "passive"))
      (node (ref "C11") (pin "-") (pinfunction "-_-") (pintype "passive"))
      (node (ref "C12") (pin "2") (pinfunction "-_2") (pintype "passive"))
      (node (ref "C13") (pin "2") (pinfunction "-_2") (pintype "passive"))
      (node (ref "C14") (pin "2") (pinfunction "-_2") (pintype "passive"))
      (node (ref "C2") (pin "2") (pinfunction "-_2") (pintype "passive"))
      (node (ref "C3") (pin "-") (pinfunction "-_-") (pintype "passive"))
      (node (ref "C4") (pin "2") (pinfunction "-_2") (pintype "passive"))
      (node (ref "C5") (pin "-") (pinfunction "-_-") (pintype "passive"))
      (node (ref "C6") (pin "2") (pinfunction "-_2") (pintype "passive"))
      (node (ref "C7") (pin "-") (pinfunction "-_-") (pintype "passive"))
      (node (ref "C8") (pin "2") (pinfunction "-_2") (pintype "passive"))
      (node (ref "C9") (pin "-") (pinfunction "-_-") (pintype "passive"))
      (node (ref "D1") (pin "K") (pinfunction "C_K") (pintype "passive"))
      (node (ref "D2") (pin "K") (pinfunction "C_K") (pintype "passive"))
      (node (ref "J1") (pin "1") (pinfunction "1_1") (pintype "passive"))
      (node (ref "J12") (pin "1") (pinfunction "1_1") (pintype "passive"))
      (node (ref "J14") (pin "1") (pinfunction "1_1") (pintype "passive"))
      (node (ref "J15") (pin "1") (pinfunction "1_1") (pintype "passive"))
      (node (ref "J17") (pin "1") (pinfunction "1_1") (pintype "passive"))
      (node (ref "J18") (pin "1") (pinfunction "1_1") (pintype "passive"))
      (node (ref "J2") (pin "1") (pinfunction "1_1") (pintype "passive"))
      (node (ref "J29") (pin "2") (pinfunction "2_2") (pintype "passive"))
      (node (ref "J3") (pin "1") (pinfunction "1_1") (pintype "passive"))
      (node (ref "J31") (pin "1") (pinfunction "GND_1") (pintype "power_in"))
      (node (ref "J31") (pin "10") (pinfunction "GND_10") (pintype "power_in"))
      (node (ref "J31") (pin "2") (pinfunction "GND_2") (pintype "power_in"))
      (node (ref "J31") (pin "3") (pinfunction "GND_3") (pintype "power_in"))
      (node (ref "J31") (pin "4") (pinfunction "GND_4") (pintype "power_in"))
      (node (ref "J31") (pin "5") (pinfunction "GND_5") (pintype "power_in"))
      (node (ref "J31") (pin "6") (pinfunction "GND_6") (pintype "power_in"))
      (node (ref "J31") (pin "7") (pinfunction "GND_7") (pintype "power_in"))
      (node (ref "J31") (pin "8") (pinfunction "GND_8") (pintype "power_in"))
      (node (ref "J31") (pin "9") (pinfunction "GND_9") (pintype "power_in"))
      (node (ref "J32") (pin "1") (pinfunction "GND_1") (pintype "power_in"))
      (node (ref "J32") (pin "10") (pinfunction "GND_10") (pintype "power_in"))
      (node (ref "J32") (pin "2") (pinfunction "GND_2") (pintype "power_in"))
      (node (ref "J32") (pin "3") (pinfunction "GND_3") (pintype "power_in"))
      (node (ref "J32") (pin "4") (pinfunction "GND_4") (pintype "power_in"))
      (node (ref "J32") (pin "5") (pinfunction "GND_5") (pintype "power_in"))
      (node (ref "J32") (pin "6") (pinfunction "GND_6") (pintype "power_in"))
      (node (ref "J32") (pin "7") (pinfunction "GND_7") (pintype "power_in"))
      (node (ref "J32") (pin "8") (pinfunction "GND_8") (pintype "power_in"))
      (node (ref "J32") (pin "9") (pinfunction "GND_9") (pintype "power_in"))
      (node (ref "J4") (pin "1") (pinfunction "1_1") (pintype "passive"))
      (node (ref "J5") (pin "1") (pinfunction "1_1") (pintype "passive"))
      (node (ref "J6") (pin "1") (pinfunction "1_1") (pintype "passive"))
      (node (ref "J7") (pin "4") (pinfunction "4_4") (pintype "passive"))
      (node (ref "J8") (pin "4") (pinfunction "4_4") (pintype "passive"))
      (node (ref "J9") (pin "4") (pinfunction "4_4") (pintype "passive"))
      (node (ref "Q1") (pin "3") (pinfunction "S_3") (pintype "bidirectional"))
      (node (ref "U$1") (pin "GND") (pinfunction "GND_GND") (pintype "power_in"))
      (node (ref "U$1") (pin "PWM_GND") (pinfunction "PWM_GND_PWM_GND") (pintype "power_in"))
      (node (ref "U$2") (pin "GND") (pinfunction "GND_GND") (pintype "power_in"))
      (node (ref "U$2") (pin "PWM_GND") (pinfunction "PWM_GND_PWM_GND") (pintype "power_in"))
      (node (ref "U$3") (pin "GND") (pinfunction "GND_GND") (pintype "power_in"))
      (node (ref "U$3") (pin "PWM_GND") (pinfunction "PWM_GND_PWM_GND") (pintype "power_in"))
      (node (ref "U$4") (pin "GND") (pinfunction "GND_GND") (pintype "power_in"))
      (node (ref "U$4") (pin "PWM_GND") (pinfunction "PWM_GND_PWM_GND") (pintype "power_in"))
      (node (ref "U$5") (pin "GND") (pinfunction "GND_GND") (pintype "power_in"))
      (node (ref "U$5") (pin "PWM_GND") (pinfunction "PWM_GND_PWM_GND") (pintype "power_in"))
      (node (ref "U$6") (pin "GND") (pinfunction "GND_GND") (pintype "power_in"))
      (node (ref "U$6") (pin "PWM_GND") (pinfunction "PWM_GND_PWM_GND") (pintype "power_in"))
    )
    (net (code "44") (name "GND_RAW") (class "Default")
      (node (ref "J11") (pin "1") (pinfunction "1_1") (pintype "passive"))
      (node (ref "J30") (pin "NEG") (pinfunction "NEG_NEG") (pintype "power_in"))
      (node (ref "Q1") (pin "2") (pinfunction "D_2") (pintype "bidirectional"))
    )
    (net (code "45") (name "I2C_VCC") (class "Default")
      (node (ref "JP5") (pin "1") (pinfunction "1_1") (pintype "passive"))
      (node (ref "JP6") (pin "1") (pinfunction "1_1") (pintype "passive"))
      (node (ref "R1") (pin "P$2") (pinfunction "2_P$2") (pintype "passive"))
      (node (ref "R2") (pin "P$2") (pinfunction "2_P$2") (pintype "passive"))
    )
    (net (code "46") (name "Net-(B1-PadA4)") (class "Default")
      (node (ref "B1") (pin "A4") (pinfunction "A4_A4") (pintype "bidirectional"))
      (node (ref "JP3") (pin "2") (pinfunction "2_2") (pintype "passive"))
    )
    (net (code "47") (name "Net-(B1-PadA5)") (class "Default")
      (node (ref "B1") (pin "A5") (pinfunction "A5_A5") (pintype "bidirectional"))
      (node (ref "JP4") (pin "2") (pinfunction "2_2") (pintype "passive"))
    )
    (net (code "48") (name "PWM1") (class "Default")
      (node (ref "B1") (pin "7") (pinfunction "7_7") (pintype "bidirectional"))
      (node (ref "J3") (pin "3") (pinfunction "3_3") (pintype "passive"))
    )
    (net (code "49") (name "PWM2") (class "Default")
      (node (ref "B1") (pin "8") (pinfunction "8_8") (pintype "bidirectional"))
      (node (ref "J4") (pin "3") (pinfunction "3_3") (pintype "passive"))
    )
    (net (code "50") (name "PWM3") (class "Default")
      (node (ref "B1") (pin "4") (pinfunction "4_4") (pintype "bidirectional"))
      (node (ref "J5") (pin "3") (pinfunction "3_3") (pintype "passive"))
    )
    (net (code "51") (name "SCL") (class "Default")
      (node (ref "B1") (pin "21") (pinfunction "21(SCL)_21") (pintype "bidirectional"))
      (node (ref "J6") (pin "3") (pinfunction "3_3") (pintype "passive"))
      (node (ref "J7") (pin "2") (pinfunction "2_2") (pintype "passive"))
      (node (ref "J8") (pin "2") (pinfunction "2_2") (pintype "passive"))
      (node (ref "J9") (pin "2") (pinfunction "2_2") (pintype "passive"))
      (node (ref "JP4") (pin "1") (pinfunction "1_1") (pintype "passive"))
      (node (ref "R1") (pin "P$1") (pinfunction "1_P$1") (pintype "passive"))
    )
    (net (code "52") (name "SDA") (class "Default")
      (node (ref "B1") (pin "20") (pinfunction "20(SDA)_20") (pintype "bidirectional"))
      (node (ref "J6") (pin "2") (pinfunction "2_2") (pintype "passive"))
      (node (ref "J7") (pin "3") (pinfunction "3_3") (pintype "passive"))
      (node (ref "J8") (pin "3") (pinfunction "3_3") (pintype "passive"))
      (node (ref "J9") (pin "3") (pinfunction "3_3") (pintype "passive"))
      (node (ref "JP3") (pin "1") (pinfunction "1_1") (pintype "passive"))
      (node (ref "R2") (pin "P$1") (pinfunction "1_P$1") (pintype "passive"))
    )
    (net (code "53") (name "unconnected-(B1-0(RX0)-Pad0)") (class "Default")
      (node (ref "B1") (pin "0") (pinfunction "0(RX0)_0") (pintype "bidirectional"))
    )
    (net (code "54") (name "unconnected-(B1-1(TX0)-Pad1)") (class "Default")
      (node (ref "B1") (pin "1") (pinfunction "1(TX0)_1") (pintype "bidirectional"))
    )
    (net (code "55") (name "unconnected-(B1-14(TX3)-Pad14)") (class "Default")
      (node (ref "B1") (pin "14") (pinfunction "14(TX3)_14") (pintype "bidirectional"))
    )
    (net (code "56") (name "unconnected-(B1-15(RX3)-Pad15)") (class "Default")
      (node (ref "B1") (pin "15") (pinfunction "15(RX3)_15") (pintype "bidirectional"))
    )
    (net (code "57") (name "unconnected-(B1-16(TX2)-Pad16)") (class "Default")
      (node (ref "B1") (pin "16") (pinfunction "16(TX2)_16") (pintype "bidirectional"))
    )
    (net (code "58") (name "unconnected-(B1-17(RX2)-Pad17)") (class "Default")
      (node (ref "B1") (pin "17") (pinfunction "17(RX2)_17") (pintype "bidirectional"))
    )
    (net (code "59") (name "unconnected-(B1-18(TX1)-Pad18)") (class "Default")
      (node (ref "B1") (pin "18") (pinfunction "18(TX1)_18") (pintype "bidirectional"))
    )
    (net (code "60") (name "unconnected-(B1-19(RX1)-Pad19)") (class "Default")
      (node (ref "B1") (pin "19") (pinfunction "19(RX1)_19") (pintype "bidirectional"))
    )
    (net (code "61") (name "unconnected-(B1-A0(RX0)-PadA0)") (class "Default")
      (node (ref "B1") (pin "A0") (pinfunction "A0(RX0)_A0") (pintype "bidirectional"))
    )
    (net (code "62") (name "unconnected-(B1-A1(TX0)-PadA1)") (class "Default")
      (node (ref "B1") (pin "A1") (pinfunction "A1(TX0)_A1") (pintype "bidirectional"))
    )
    (net (code "63") (name "unconnected-(B1-Pad2)") (class "Default")
      (node (ref "B1") (pin "2") (pinfunction "2_2") (pintype "bidirectional"))
    )
    (net (code "64") (name "unconnected-(B1-Pad12)") (class "Default")
      (node (ref "B1") (pin "12") (pinfunction "12_12") (pintype "bidirectional"))
    )
    (net (code "65") (name "unconnected-(B1-Pad13)") (class "Default")
      (node (ref "B1") (pin "13") (pinfunction "13_13") (pintype "bidirectional"))
    )
    (net (code "66") (name "unconnected-(B1-Pad22)") (class "Default")
      (node (ref "B1") (pin "22") (pinfunction "22_22") (pintype "bidirectional"))
    )
    (net (code "67") (name "unconnected-(B1-Pad23)") (class "Default")
      (node (ref "B1") (pin "23") (pinfunction "23_23") (pintype "bidirectional"))
    )
    (net (code "68") (name "unconnected-(B1-Pad24)") (class "Default")
      (node (ref "B1") (pin "24") (pinfunction "24_24") (pintype "bidirectional"))
    )
    (net (code "69") (name "unconnected-(B1-Pad25)") (class "Default")
      (node (ref "B1") (pin "25") (pinfunction "25_25") (pintype "bidirectional"))
    )
    (net (code "70") (name "unconnected-(B1-Pad26)") (class "Default")
      (node (ref "B1") (pin "26") (pinfunction "26_26") (pintype "bidirectional"))
    )
    (net (code "71") (name "unconnected-(B1-Pad27)") (class "Default")
      (node (ref "B1") (pin "27") (pinfunction "27_27") (pintype "bidirectional"))
    )
    (net (code "72") (name "unconnected-(B1-Pad28)") (class "Default")
      (node (ref "B1") (pin "28") (pinfunction "28_28") (pintype "bidirectional"))
    )
    (net (code "73") (name "unconnected-(B1-Pad29)") (class "Default")
      (node (ref "B1") (pin "29") (pinfunction "29_29") (pintype "bidirectional"))
    )
    (net (code "74") (name "unconnected-(B1-Pad30)") (class "Default")
      (node (ref "B1") (pin "30") (pinfunction "30_30") (pintype "bidirectional"))
    )
    (net (code "75") (name "unconnected-(B1-Pad31)") (class "Default")
      (node (ref "B1") (pin "31") (pinfunction "31_31") (pintype "bidirectional"))
    )
    (net (code "76") (name "unconnected-(B1-Pad32)") (class "Default")
      (node (ref "B1") (pin "32") (pinfunction "32_32") (pintype "bidirectional"))
    )
    (net (code "77") (name "unconnected-(B1-Pad33)") (class "Default")
      (node (ref "B1") (pin "33") (pinfunction "33_33") (pintype "bidirectional"))
    )
    (net (code "78") (name "unconnected-(B1-Pad34)") (class "Default")
      (node (ref "B1") (pin "34") (pinfunction "34_34") (pintype "bidirectional"))
    )
    (net (code "79") (name "unconnected-(B1-Pad35)") (class "Default")
      (node (ref "B1") (pin "35") (pinfunction "35_35") (pintype "bidirectional"))
    )
    (net (code "80") (name "unconnected-(B1-Pad36)") (class "Default")
      (node (ref "B1") (pin "36") (pinfunction "36_36") (pintype "bidirectional"))
    )
    (net (code "81") (name "unconnected-(B1-Pad37)") (class "Default")
      (node (ref "B1") (pin "37") (pinfunction "37_37") (pintype "bidirectional"))
    )
    (net (code "82") (name "unconnected-(B1-Pad38)") (class "Default")
      (node (ref "B1") (pin "38") (pinfunction "38_38") (pintype "bidirectional"))
    )
    (net (code "83") (name "unconnected-(B1-Pad39)") (class "Default")
      (node (ref "B1") (pin "39") (pinfunction "39_39") (pintype "bidirectional"))
    )
    (net (code "84") (name "unconnected-(B1-Pad40)") (class "Default")
      (node (ref "B1") (pin "40") (pinfunction "40_40") (pintype "bidirectional"))
    )
    (net (code "85") (name "unconnected-(B1-Pad41)") (class "Default")
      (node (ref "B1") (pin "41") (pinfunction "41_41") (pintype "bidirectional"))
    )
    (net (code "86") (name "unconnected-(B1-Pad42)") (class "Default")
      (node (ref "B1") (pin "42") (pinfunction "42_42") (pintype "bidirectional"))
    )
    (net (code "87") (name "unconnected-(B1-Pad43)") (class "Default")
      (node (ref "B1") (pin "43") (pinfunction "43_43") (pintype "bidirectional"))
    )
    (net (code "88") (name "unconnected-(B1-Pad44)") (class "Default")
      (node (ref "B1") (pin "44") (pinfunction "44_44") (pintype "bidirectional"))
    )
    (net (code "89") (name "unconnected-(B1-Pad45)") (class "Default")
      (node (ref "B1") (pin "45") (pinfunction "45_45") (pintype "bidirectional"))
    )
    (net (code "90") (name "unconnected-(B1-Pad46)") (class "Default")
      (node (ref "B1") (pin "46") (pinfunction "46_46") (pintype "bidirectional"))
    )
    (net (code "91") (name "unconnected-(B1-Pad47)") (class "Default")
      (node (ref "B1") (pin "47") (pinfunction "47_47") (pintype "bidirectional"))
    )
    (net (code "92") (name "unconnected-(B1-Pad48)") (class "Default")
      (node (ref "B1") (pin "48") (pinfunction "48_48") (pintype "bidirectional"))
    )
    (net (code "93") (name "unconnected-(B1-Pad49)") (class "Default")
      (node (ref "B1") (pin "49") (pinfunction "49_49") (pintype "bidirectional"))
    )
    (net (code "94") (name "unconnected-(B1-Pad50)") (class "Default")
      (node (ref "B1") (pin "50") (pinfunction "50_50") (pintype "bidirectional"))
    )
    (net (code "95") (name "unconnected-(B1-Pad51)") (class "Default")
      (node (ref "B1") (pin "51") (pinfunction "51_51") (pintype "bidirectional"))
    )
    (net (code "96") (name "unconnected-(B1-Pad52)") (class "Default")
      (node (ref "B1") (pin "52") (pinfunction "52_52") (pintype "bidirectional"))
    )
    (net (code "97") (name "unconnected-(B1-Pad53)") (class "Default")
      (node (ref "B1") (pin "53") (pinfunction "53_53") (pintype "bidirectional"))
    )
    (net (code "98") (name "unconnected-(B1-PadA2)") (class "Default")
      (node (ref "B1") (pin "A2") (pinfunction "A2_A2") (pintype "bidirectional"))
    )
    (net (code "99") (name "unconnected-(B1-PadA3)") (class "Default")
      (node (ref "B1") (pin "A3") (pinfunction "A3_A3") (pintype "bidirectional"))
    )
    (net (code "100") (name "unconnected-(B1-PadA6)") (class "Default")
      (node (ref "B1") (pin "A6") (pinfunction "A6_A6") (pintype "bidirectional"))
    )
    (net (code "101") (name "unconnected-(B1-PadA7)") (class "Default")
      (node (ref "B1") (pin "A7") (pinfunction "A7_A7") (pintype "bidirectional"))
    )
    (net (code "102") (name "unconnected-(B1-PadA8)") (class "Default")
      (node (ref "B1") (pin "A8") (pinfunction "A8_A8") (pintype "bidirectional"))
    )
    (net (code "103") (name "unconnected-(B1-PadA9)") (class "Default")
      (node (ref "B1") (pin "A9") (pinfunction "A9_A9") (pintype "bidirectional"))
    )
    (net (code "104") (name "unconnected-(B1-PadA10)") (class "Default")
      (node (ref "B1") (pin "A10") (pinfunction "A10_A10") (pintype "bidirectional"))
    )
    (net (code "105") (name "unconnected-(B1-PadA11)") (class "Default")
      (node (ref "B1") (pin "A11") (pinfunction "A11_A11") (pintype "bidirectional"))
    )
    (net (code "106") (name "unconnected-(B1-PadA12)") (class "Default")
      (node (ref "B1") (pin "A12") (pinfunction "A12_A12") (pintype "bidirectional"))
    )
    (net (code "107") (name "unconnected-(B1-PadA13)") (class "Default")
      (node (ref "B1") (pin "A13") (pinfunction "A13_A13") (pintype "bidirectional"))
    )
    (net (code "108") (name "unconnected-(B1-PadA14)") (class "Default")
      (node (ref "B1") (pin "A14") (pinfunction "A14_A14") (pintype "bidirectional"))
    )
    (net (code "109") (name "unconnected-(B1-PadA15)") (class "Default")
      (node (ref "B1") (pin "A15") (pinfunction "A15_A15") (pintype "bidirectional"))
    )
    (net (code "110") (name "unconnected-(B1-PadAREF)") (class "Default")
      (node (ref "B1") (pin "AREF") (pinfunction "AREF_AREF") (pintype "bidirectional"))
    )
    (net (code "111") (name "unconnected-(B1-PadRESET)") (class "Default")
      (node (ref "B1") (pin "RESET") (pinfunction "RESET_RESET") (pintype "bidirectional"))
    )
    (net (code "112") (name "unconnected-(B1-PadVIN)") (class "Default")
      (node (ref "B1") (pin "VIN") (pinfunction "VIN_VIN") (pintype "bidirectional"))
    )
  )
)
